# 03-POWER_CTRL.net
KiCad netlist of a schematic drawn in Altium Designer
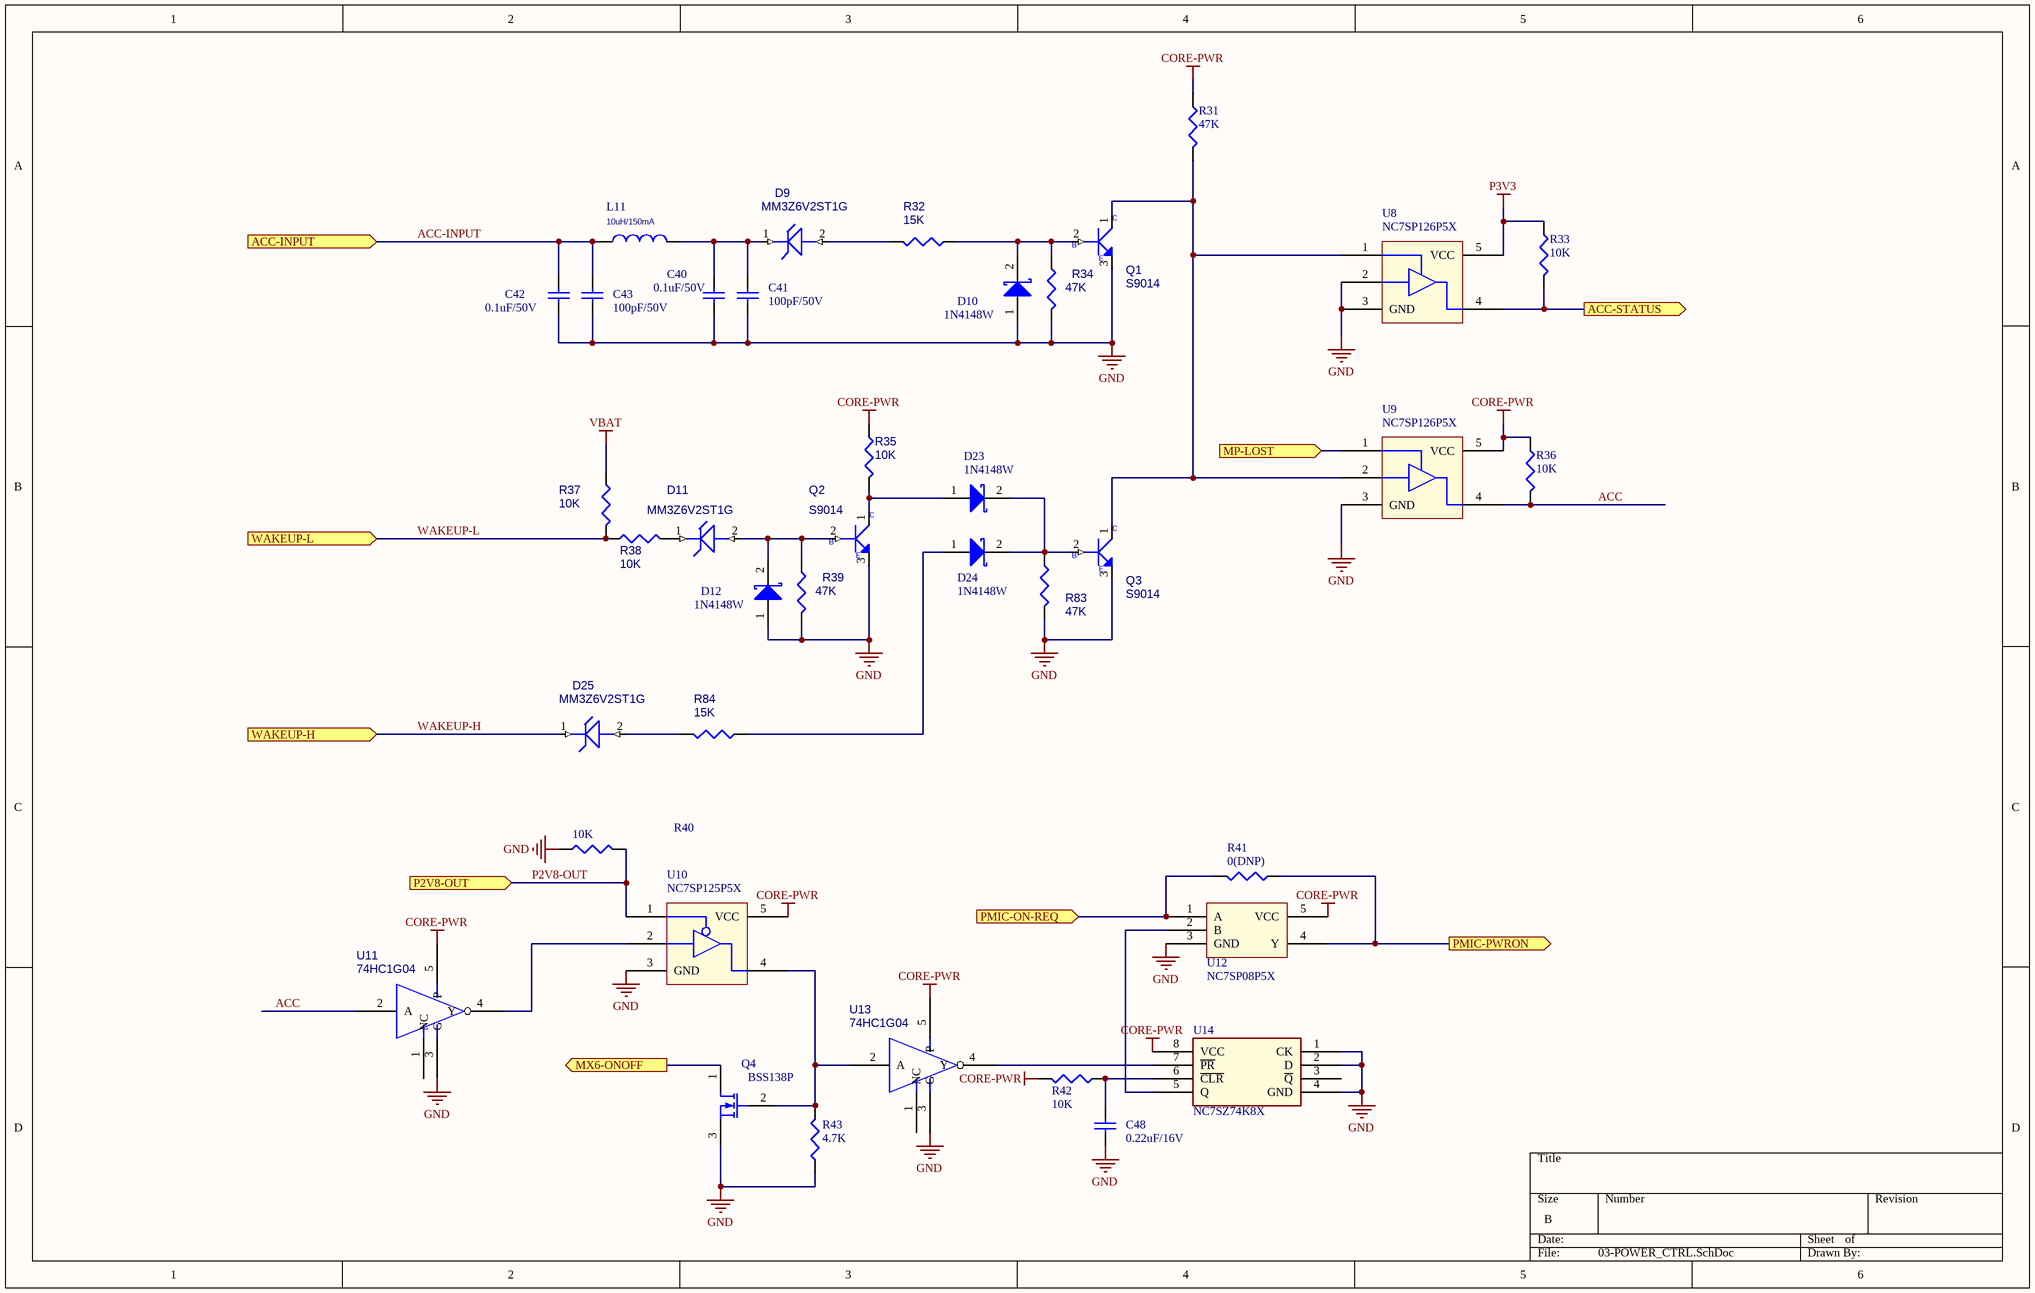
[diagram p0: 03-POWER_CTRL.SchDoc]

(export (version "E")
  (design (tool "Eeschema 10.0.6"))
  (components
    (comp (ref "C40")
      (value "0.1uF/50V")
      (footprint "0402")
      (description "Capacitor")
      (fields (field (name "PUBLISHER") "Altium Limited"))
      (libsource (lib "Miscellaneous Devices") (part "Cap"))
    )
    (comp (ref "C41")
      (value "100pF/50V")
      (footprint "0402")
      (description "Capacitor")
      (fields (field (name "PUBLISHER") "Altium Limited"))
      (libsource (lib "Miscellaneous Devices") (part "Cap"))
    )
    (comp (ref "C42")
      (value "0.1uF/50V")
      (footprint "0402")
      (description "Capacitor")
      (fields (field (name "PUBLISHER") "Altium Limited"))
      (libsource (lib "Miscellaneous Devices") (part "Cap"))
    )
    (comp (ref "C43")
      (value "100pF/50V")
      (footprint "0402")
      (description "Capacitor")
      (fields (field (name "PUBLISHER") "Altium Limited"))
      (libsource (lib "Miscellaneous Devices") (part "Cap"))
    )
    (comp (ref "C48")
      (value "0.22uF/16V")
      (footprint "0402")
      (description "Capacitor")
      (fields (field (name "PUBLISHER") "Altium Limited"))
      (libsource (lib "Miscellaneous Devices") (part "Cap"))
    )
    (comp (ref "D9")
      (value "MM3Z6V2ST1G")
      (footprint "SOD323")
      (libsource (lib "*") (part "MMGZ5231BPTLL34"))
    )
    (comp (ref "D10")
      (value "1N4148W")
      (footprint "SOD123")
      (description "Schottky Rectifier")
      (libsource (lib "Miscellaneous Devices") (part "Diode 11DQ03"))
    )
    (comp (ref "D11")
      (value "MM3Z6V2ST1G")
      (footprint "SOD323")
      (libsource (lib "*") (part "MMGZ5231BPTLL34"))
    )
    (comp (ref "D12")
      (value "1N4148W")
      (footprint "SOD123")
      (description "Schottky Rectifier")
      (libsource (lib "Miscellaneous Devices") (part "Diode 11DQ03"))
    )
    (comp (ref "D23")
      (value "1N4148W")
      (footprint "SOD123")
      (description "Schottky Rectifier")
      (libsource (lib "Miscellaneous Devices") (part "Diode 11DQ03"))
    )
    (comp (ref "D24")
      (value "1N4148W")
      (footprint "SOD123")
      (description "Schottky Rectifier")
      (libsource (lib "Miscellaneous Devices") (part "Diode 11DQ03"))
    )
    (comp (ref "D25")
      (value "MM3Z6V2ST1G")
      (footprint "SOD323")
      (libsource (lib "*") (part "MMGZ5231BPTLL34"))
    )
    (comp (ref "L11") (value "10uH/150mA") (libsource (lib "*") (part "L_0")))
    (comp (ref "Q1")
      (value "S9014")
      (footprint "NPN")
      (fields (field (name "PART NUMBER") "SB039040000"))
      (libsource (lib "*") (part "MMBT3904_NL_SOT23-3"))
    )
    (comp (ref "Q2")
      (value "S9014")
      (footprint "NPN")
      (fields (field (name "PART NUMBER") "SB039040000"))
      (libsource (lib "*") (part "MMBT3904_NL_SOT23-3"))
    )
    (comp (ref "Q3")
      (value "S9014")
      (footprint "NPN")
      (fields (field (name "PART NUMBER") "SB039040000"))
      (libsource (lib "*") (part "MMBT3904_NL_SOT23-3"))
    )
    (comp (ref "Q4")
      (value "BSS138P")
      (footprint "NPN")
      (description "N-Channel MOSFET")
      (fields (field (name "PUBLISHER") "Altium Limited"))
      (libsource (lib "Miscellaneous Devices") (part "MOSFET-N"))
    )
    (comp (ref "R31") (value "47K") (footprint "0402") (libsource (lib "*") (part "CR16-1003FM")))
    (comp (ref "R32") (value "15K") (libsource (lib "*") (part "R")))
    (comp (ref "R33") (value "10K") (footprint "0402") (libsource (lib "*") (part "CR16-1003FM")))
    (comp (ref "R34") (value "47K") (libsource (lib "*") (part "R")))
    (comp (ref "R35") (value "10K") (libsource (lib "*") (part "R")))
    (comp (ref "R36") (value "10K") (footprint "0402") (libsource (lib "*") (part "CR16-1003FM")))
    (comp (ref "R37") (value "10K") (libsource (lib "*") (part "R")))
    (comp (ref "R38") (value "10K") (libsource (lib "*") (part "R")))
    (comp (ref "R39") (value "47K") (libsource (lib "*") (part "R")))
    (comp (ref "R40") (value "10K") (footprint "0402") (libsource (lib "*") (part "CR16-1003FM")))
    (comp (ref "R41")
      (value "0(DNP)")
      (footprint "0402")
      (description "Resistor")
      (fields (field (name "PUBLISHER") "Altium Limited"))
      (libsource (lib "Miscellaneous Devices") (part "Res3"))
    )
    (comp (ref "R42")
      (value "10K")
      (footprint "0402")
      (description "Resistor")
      (fields (field (name "PUBLISHER") "Altium Limited"))
      (libsource (lib "Miscellaneous Devices") (part "Res3"))
    )
    (comp (ref "R43")
      (value "4.7K")
      (footprint "0402")
      (description "Resistor")
      (fields (field (name "PUBLISHER") "Altium Limited"))
      (libsource (lib "Miscellaneous Devices") (part "Res3"))
    )
    (comp (ref "R83") (value "47K") (libsource (lib "*") (part "R")))
    (comp (ref "R84") (value "15K") (libsource (lib "*") (part "R")))
    (comp (ref "U8") (value "NC7SP126P5X") (footprint "SC70") (libsource (lib "Schlib") (part "NC7SP126P5X")))
    (comp (ref "U9") (value "NC7SP126P5X") (footprint "SC70") (libsource (lib "Schlib") (part "NC7SP126P5X")))
    (comp (ref "U10")
      (value "NC7SP125P5X")
      (footprint "SC70")
      (libsource (lib "Schlib") (part "NC7SP125P5X"))
    )
    (comp (ref "U11") (value "74HC1G04") (libsource (lib "*") (part "74LVC1G04GW_SOT353-5")))
    (comp (ref "U12") (value "NC7SP08P5X") (footprint "SC70") (libsource (lib "Schlib") (part "NC7SP08P5X")))
    (comp (ref "U13") (value "74HC1G04") (libsource (lib "*") (part "74LVC1G04GW_SOT353-5")))
    (comp (ref "U14")
      (value "NC7SZ74K8X")
      (footprint "US8")
      (description "IC;NC7SZ74,D-TYPE FLIP-FLOP,US8")
      (libsource (lib "*") (part "NC7SZ74-US8_0"))
    )
  )
  (nets
    (net (code "1") (name "/ACC") (class "Default")
      (node (ref "R36") (pin "2") (pinfunction "2_2") (pintype "passive"))
      (node (ref "U11") (pin "2") (pinfunction "A_2") (pintype "passive"))
      (node (ref "U9") (pin "4") (pinfunction "Y_4") (pintype "passive"))
    )
    (net (code "2") (name "/ACC-INPUT") (class "Default")
      (node (ref "C42") (pin "1") (pinfunction "1_1") (pintype "passive"))
      (node (ref "C43") (pin "1") (pinfunction "1_1") (pintype "passive"))
      (node (ref "L11") (pin "2") (pinfunction "2_2") (pintype "passive"))
    )
    (net (code "3") (name "/ACC-STATUS") (class "Default")
      (node (ref "R33") (pin "2") (pinfunction "2_2") (pintype "passive"))
      (node (ref "U8") (pin "4") (pinfunction "Y_4") (pintype "passive"))
    )
    (net (code "4") (name "/MP-LOST") (class "Default")
      (node (ref "U9") (pin "1") (pinfunction "OE_1") (pintype "passive"))
    )
    (net (code "5") (name "/MX6-ONOFF") (class "Default")
      (node (ref "Q4") (pin "1") (pinfunction "D_1") (pintype "passive"))
    )
    (net (code "6") (name "/P2V8-OUT") (class "Default")
      (node (ref "R40") (pin "1") (pinfunction "1_1") (pintype "passive"))
      (node (ref "U10") (pin "1") (pinfunction "OE_1") (pintype "passive"))
    )
    (net (code "7") (name "/PMIC-ON-REQ") (class "Default")
      (node (ref "R41") (pin "1") (pinfunction "1_1") (pintype "passive"))
      (node (ref "U12") (pin "1") (pinfunction "A_1") (pintype "passive"))
    )
    (net (code "8") (name "/PMIC-PWRON") (class "Default")
      (node (ref "R41") (pin "2") (pinfunction "2_2") (pintype "passive"))
      (node (ref "U12") (pin "4") (pinfunction "Y_4") (pintype "passive"))
    )
    (net (code "9") (name "/WAKEUP-H") (class "Default")
      (node (ref "D25") (pin "1") (pinfunction "1_1") (pintype "input"))
    )
    (net (code "10") (name "/WAKEUP-L") (class "Default")
      (node (ref "R37") (pin "2") (pinfunction "2_2") (pintype "passive"))
      (node (ref "R38") (pin "1") (pinfunction "1_1") (pintype "passive"))
    )
    (net (code "11") (name "CORE-PWR") (class "Default")
      (node (ref "R31") (pin "1") (pinfunction "1_1") (pintype "passive"))
      (node (ref "R35") (pin "1") (pinfunction "1_1") (pintype "passive"))
      (node (ref "R36") (pin "1") (pinfunction "1_1") (pintype "passive"))
      (node (ref "R42") (pin "1") (pinfunction "1_1") (pintype "passive"))
      (node (ref "U10") (pin "5") (pinfunction "VCC_5") (pintype "passive"))
      (node (ref "U11") (pin "5") (pinfunction "P_5") (pintype "passive"))
      (node (ref "U12") (pin "5") (pinfunction "VCC_5") (pintype "passive"))
      (node (ref "U13") (pin "5") (pinfunction "P_5") (pintype "passive"))
      (node (ref "U14") (pin "8") (pinfunction "VCC_8") (pintype "passive"))
      (node (ref "U9") (pin "5") (pinfunction "VCC_5") (pintype "passive"))
    )
    (net (code "12") (name "GND") (class "Default")
      (node (ref "C40") (pin "2") (pinfunction "2_2") (pintype "passive"))
      (node (ref "C41") (pin "2") (pinfunction "2_2") (pintype "passive"))
      (node (ref "C42") (pin "2") (pinfunction "2_2") (pintype "passive"))
      (node (ref "C43") (pin "2") (pinfunction "2_2") (pintype "passive"))
      (node (ref "C48") (pin "2") (pinfunction "2_2") (pintype "passive"))
      (node (ref "D10") (pin "1") (pinfunction "A_1") (pintype "passive"))
      (node (ref "D12") (pin "1") (pinfunction "A_1") (pintype "passive"))
      (node (ref "Q1") (pin "3") (pinfunction "EMITTER_3") (pintype "passive"))
      (node (ref "Q2") (pin "3") (pinfunction "EMITTER_3") (pintype "passive"))
      (node (ref "Q3") (pin "3") (pinfunction "EMITTER_3") (pintype "passive"))
      (node (ref "Q4") (pin "3") (pinfunction "S_3") (pintype "passive"))
      (node (ref "R34") (pin "2") (pinfunction "2_2") (pintype "passive"))
      (node (ref "R39") (pin "2") (pinfunction "2_2") (pintype "passive"))
      (node (ref "R40") (pin "2") (pinfunction "2_2") (pintype "passive"))
      (node (ref "R43") (pin "2") (pinfunction "2_2") (pintype "passive"))
      (node (ref "R83") (pin "2") (pinfunction "2_2") (pintype "passive"))
      (node (ref "U10") (pin "3") (pinfunction "GND_3") (pintype "passive"))
      (node (ref "U11") (pin "3") (pinfunction "G_3") (pintype "passive"))
      (node (ref "U12") (pin "3") (pinfunction "GND_3") (pintype "passive"))
      (node (ref "U13") (pin "3") (pinfunction "G_3") (pintype "passive"))
      (node (ref "U14") (pin "1") (pinfunction "CK_1") (pintype "passive"))
      (node (ref "U14") (pin "2") (pinfunction "D_2") (pintype "passive"))
      (node (ref "U14") (pin "4") (pinfunction "GND_4") (pintype "passive"))
      (node (ref "U8") (pin "2") (pinfunction "A_2") (pintype "passive"))
      (node (ref "U8") (pin "3") (pinfunction "GND_3") (pintype "passive"))
      (node (ref "U9") (pin "3") (pinfunction "GND_3") (pintype "passive"))
    )
    (net (code "13") (name "Net-(C40-Pad1)") (class "Default")
      (node (ref "C40") (pin "1") (pinfunction "1_1") (pintype "passive"))
      (node (ref "C41") (pin "1") (pinfunction "1_1") (pintype "passive"))
      (node (ref "D9") (pin "1") (pinfunction "1_1") (pintype "input"))
      (node (ref "L11") (pin "1") (pinfunction "1_1") (pintype "passive"))
    )
    (net (code "14") (name "Net-(D9-Pad2)") (class "Default")
      (node (ref "D9") (pin "2") (pinfunction "2_2") (pintype "input"))
      (node (ref "R32") (pin "2") (pinfunction "2_2") (pintype "passive"))
    )
    (net (code "15") (name "Net-(D10-K)") (class "Default")
      (node (ref "D10") (pin "2") (pinfunction "K_2") (pintype "passive"))
      (node (ref "Q1") (pin "2") (pinfunction "BASE_2") (pintype "input"))
      (node (ref "R32") (pin "1") (pinfunction "1_1") (pintype "passive"))
      (node (ref "R34") (pin "1") (pinfunction "1_1") (pintype "passive"))
    )
    (net (code "16") (name "Net-(D11-Pad1)") (class "Default")
      (node (ref "D11") (pin "1") (pinfunction "1_1") (pintype "input"))
      (node (ref "R38") (pin "2") (pinfunction "2_2") (pintype "passive"))
    )
    (net (code "17") (name "Net-(D12-K)") (class "Default")
      (node (ref "D11") (pin "2") (pinfunction "2_2") (pintype "input"))
      (node (ref "D12") (pin "2") (pinfunction "K_2") (pintype "passive"))
      (node (ref "Q2") (pin "2") (pinfunction "BASE_2") (pintype "input"))
      (node (ref "R39") (pin "1") (pinfunction "1_1") (pintype "passive"))
    )
    (net (code "18") (name "Net-(D23-A)") (class "Default")
      (node (ref "D23") (pin "1") (pinfunction "A_1") (pintype "passive"))
      (node (ref "Q2") (pin "1") (pinfunction "COLLECTOR_1") (pintype "passive"))
      (node (ref "R35") (pin "2") (pinfunction "2_2") (pintype "passive"))
    )
    (net (code "19") (name "Net-(D23-K)") (class "Default")
      (node (ref "D23") (pin "2") (pinfunction "K_2") (pintype "passive"))
      (node (ref "D24") (pin "2") (pinfunction "K_2") (pintype "passive"))
      (node (ref "Q3") (pin "2") (pinfunction "BASE_2") (pintype "input"))
      (node (ref "R83") (pin "1") (pinfunction "1_1") (pintype "passive"))
    )
    (net (code "20") (name "Net-(D24-A)") (class "Default")
      (node (ref "D24") (pin "1") (pinfunction "A_1") (pintype "passive"))
      (node (ref "R84") (pin "1") (pinfunction "1_1") (pintype "passive"))
    )
    (net (code "21") (name "Net-(D25-Pad2)") (class "Default")
      (node (ref "D25") (pin "2") (pinfunction "2_2") (pintype "input"))
      (node (ref "R84") (pin "2") (pinfunction "2_2") (pintype "passive"))
    )
    (net (code "22") (name "Net-(Q1-COLLECTOR)") (class "Default")
      (node (ref "Q1") (pin "1") (pinfunction "COLLECTOR_1") (pintype "passive"))
      (node (ref "Q3") (pin "1") (pinfunction "COLLECTOR_1") (pintype "passive"))
      (node (ref "R31") (pin "2") (pinfunction "2_2") (pintype "passive"))
      (node (ref "U8") (pin "1") (pinfunction "OE_1") (pintype "passive"))
      (node (ref "U9") (pin "2") (pinfunction "A_2") (pintype "passive"))
    )
    (net (code "23") (name "Net-(Q4-G)") (class "Default")
      (node (ref "Q4") (pin "2") (pinfunction "G_2") (pintype "passive"))
      (node (ref "R43") (pin "1") (pinfunction "1_1") (pintype "passive"))
      (node (ref "U10") (pin "4") (pinfunction "Y_4") (pintype "passive"))
      (node (ref "U13") (pin "2") (pinfunction "A_2") (pintype "passive"))
    )
    (net (code "24") (name "Net-(U10-A)") (class "Default")
      (node (ref "U10") (pin "2") (pinfunction "A_2") (pintype "passive"))
      (node (ref "U11") (pin "4") (pinfunction "Y_4") (pintype "passive"))
    )
    (net (code "25") (name "Net-(U12-B)") (class "Default")
      (node (ref "U12") (pin "2") (pinfunction "B_2") (pintype "passive"))
      (node (ref "U14") (pin "5") (pinfunction "Q_5") (pintype "passive"))
    )
    (net (code "26") (name "Net-(U13-Y)") (class "Default")
      (node (ref "U13") (pin "4") (pinfunction "Y_4") (pintype "passive"))
      (node (ref "U14") (pin "7") (pinfunction "~{PR}_7") (pintype "passive"))
    )
    (net (code "27") (name "Net-(U14-~{CLR})") (class "Default")
      (node (ref "C48") (pin "1") (pinfunction "1_1") (pintype "passive"))
      (node (ref "R42") (pin "2") (pinfunction "2_2") (pintype "passive"))
      (node (ref "U14") (pin "6") (pinfunction "~{CLR}_6") (pintype "passive"))
    )
    (net (code "28") (name "P3V3") (class "Default")
      (node (ref "R33") (pin "1") (pinfunction "1_1") (pintype "passive"))
      (node (ref "U8") (pin "5") (pinfunction "VCC_5") (pintype "passive"))
    )
    (net (code "29") (name "VBAT") (class "Default")
      (node (ref "R37") (pin "1") (pinfunction "1_1") (pintype "passive"))
    )
    (net (code "30") (name "unconnected-(U11-NC-Pad1)") (class "Default")
      (node (ref "U11") (pin "1") (pinfunction "NC_1") (pintype "passive"))
    )
    (net (code "31") (name "unconnected-(U13-NC-Pad1)") (class "Default")
      (node (ref "U13") (pin "1") (pinfunction "NC_1") (pintype "passive"))
    )
    (net (code "32") (name "unconnected-(U14-~{Q}-Pad3)") (class "Default")
      (node (ref "U14") (pin "3") (pinfunction "~{Q}_3") (pintype "passive"))
    )
  )
)
